# Esp8266_DevBoard.net
KiCad netlist of a schematic drawn in EAGLE
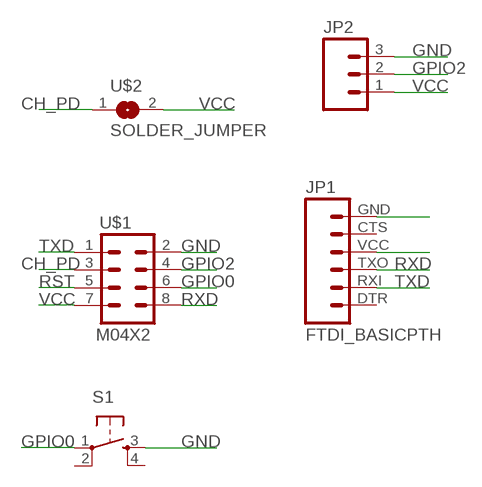
[diagram p0: schematic, sheet 1]

(export (version "E")
  (design (tool "Eeschema 10.0.6"))
  (components
    (comp (ref "JP1")
      (value "FTDI_BASICPTH")
      (footprint "eagle-import:FTDI_BASIC")
      (libsource (lib "eagle-import") (part "FTDI_BASICPTH"))
    )
    (comp (ref "JP2")
      (value "M03PTH")
      (footprint "eagle-import:1X03")
      (libsource (lib "eagle-import") (part "M03PTH"))
    )
    (comp (ref "S1")
      (value "6MM_SWITCH6MM_SWITCH")
      (footprint "eagle-import:6MM_SWITCH")
      (libsource (lib "eagle-import") (part "6MM_SWITCH6MM_SWITCH"))
    )
    (comp (ref "U$1")
      (value "M04X2")
      (footprint "eagle-import:2X4")
      (libsource (lib "eagle-import") (part "M04X2"))
    )
    (comp (ref "U$2")
      (value "SOLDER_JUMPER")
      (footprint "eagle-import:SJFAB")
      (libsource (lib "eagle-import") (part "SOLDER_JUMPER"))
    )
  )
  (nets
    (net (code "1") (name "/CH_PD") (class "Default")
      (node (ref "U$1") (pin "3") (pinfunction "3_3") (pintype "passive"))
      (node (ref "U$2") (pin "1") (pinfunction "1_1") (pintype "passive"))
    )
    (net (code "2") (name "/GND") (class "Default")
      (node (ref "JP1") (pin "GND") (pinfunction "6_GND") (pintype "passive"))
      (node (ref "JP2") (pin "3") (pinfunction "3_3") (pintype "passive"))
      (node (ref "S1") (pin "3") (pinfunction "S_3") (pintype "passive"))
      (node (ref "U$1") (pin "2") (pinfunction "2_2") (pintype "passive"))
    )
    (net (code "3") (name "/GPIO0") (class "Default")
      (node (ref "S1") (pin "1") (pinfunction "P_1") (pintype "passive"))
      (node (ref "U$1") (pin "6") (pinfunction "6_6") (pintype "passive"))
    )
    (net (code "4") (name "/GPIO2") (class "Default")
      (node (ref "JP2") (pin "2") (pinfunction "2_2") (pintype "passive"))
      (node (ref "U$1") (pin "4") (pinfunction "4_4") (pintype "passive"))
    )
    (net (code "5") (name "/RST") (class "Default")
      (node (ref "U$1") (pin "5") (pinfunction "5_5") (pintype "passive"))
    )
    (net (code "6") (name "/RXD") (class "Default")
      (node (ref "JP1") (pin "TXO") (pinfunction "3_TXO") (pintype "passive"))
      (node (ref "U$1") (pin "8") (pinfunction "8_8") (pintype "passive"))
    )
    (net (code "7") (name "/TXD") (class "Default")
      (node (ref "JP1") (pin "RXI") (pinfunction "2_RXI") (pintype "passive"))
      (node (ref "U$1") (pin "1") (pinfunction "1_1") (pintype "passive"))
    )
    (net (code "8") (name "/VCC") (class "Default")
      (node (ref "JP1") (pin "VCC") (pinfunction "4_VCC") (pintype "passive"))
      (node (ref "JP2") (pin "1") (pinfunction "1_1") (pintype "passive"))
      (node (ref "U$1") (pin "7") (pinfunction "7_7") (pintype "passive"))
      (node (ref "U$2") (pin "2") (pinfunction "2_2") (pintype "passive"))
    )
    (net (code "9") (name "unconnected-(JP1-1-PadDTR)") (class "Default")
      (node (ref "JP1") (pin "DTR") (pinfunction "1_DTR") (pintype "passive"))
    )
    (net (code "10") (name "unconnected-(JP1-5-PadCTS)") (class "Default")
      (node (ref "JP1") (pin "CTS") (pinfunction "5_CTS") (pintype "passive"))
    )
    (net (code "11") (name "unconnected-(S1-P1-Pad2)") (class "Default")
      (node (ref "S1") (pin "2") (pinfunction "P1_2") (pintype "passive"))
    )
    (net (code "12") (name "unconnected-(S1-S1-Pad4)") (class "Default")
      (node (ref "S1") (pin "4") (pinfunction "S1_4") (pintype "passive"))
    )
  )
)
